# WiFiRadio.net
KiCad netlist of a schematic drawn in EAGLE
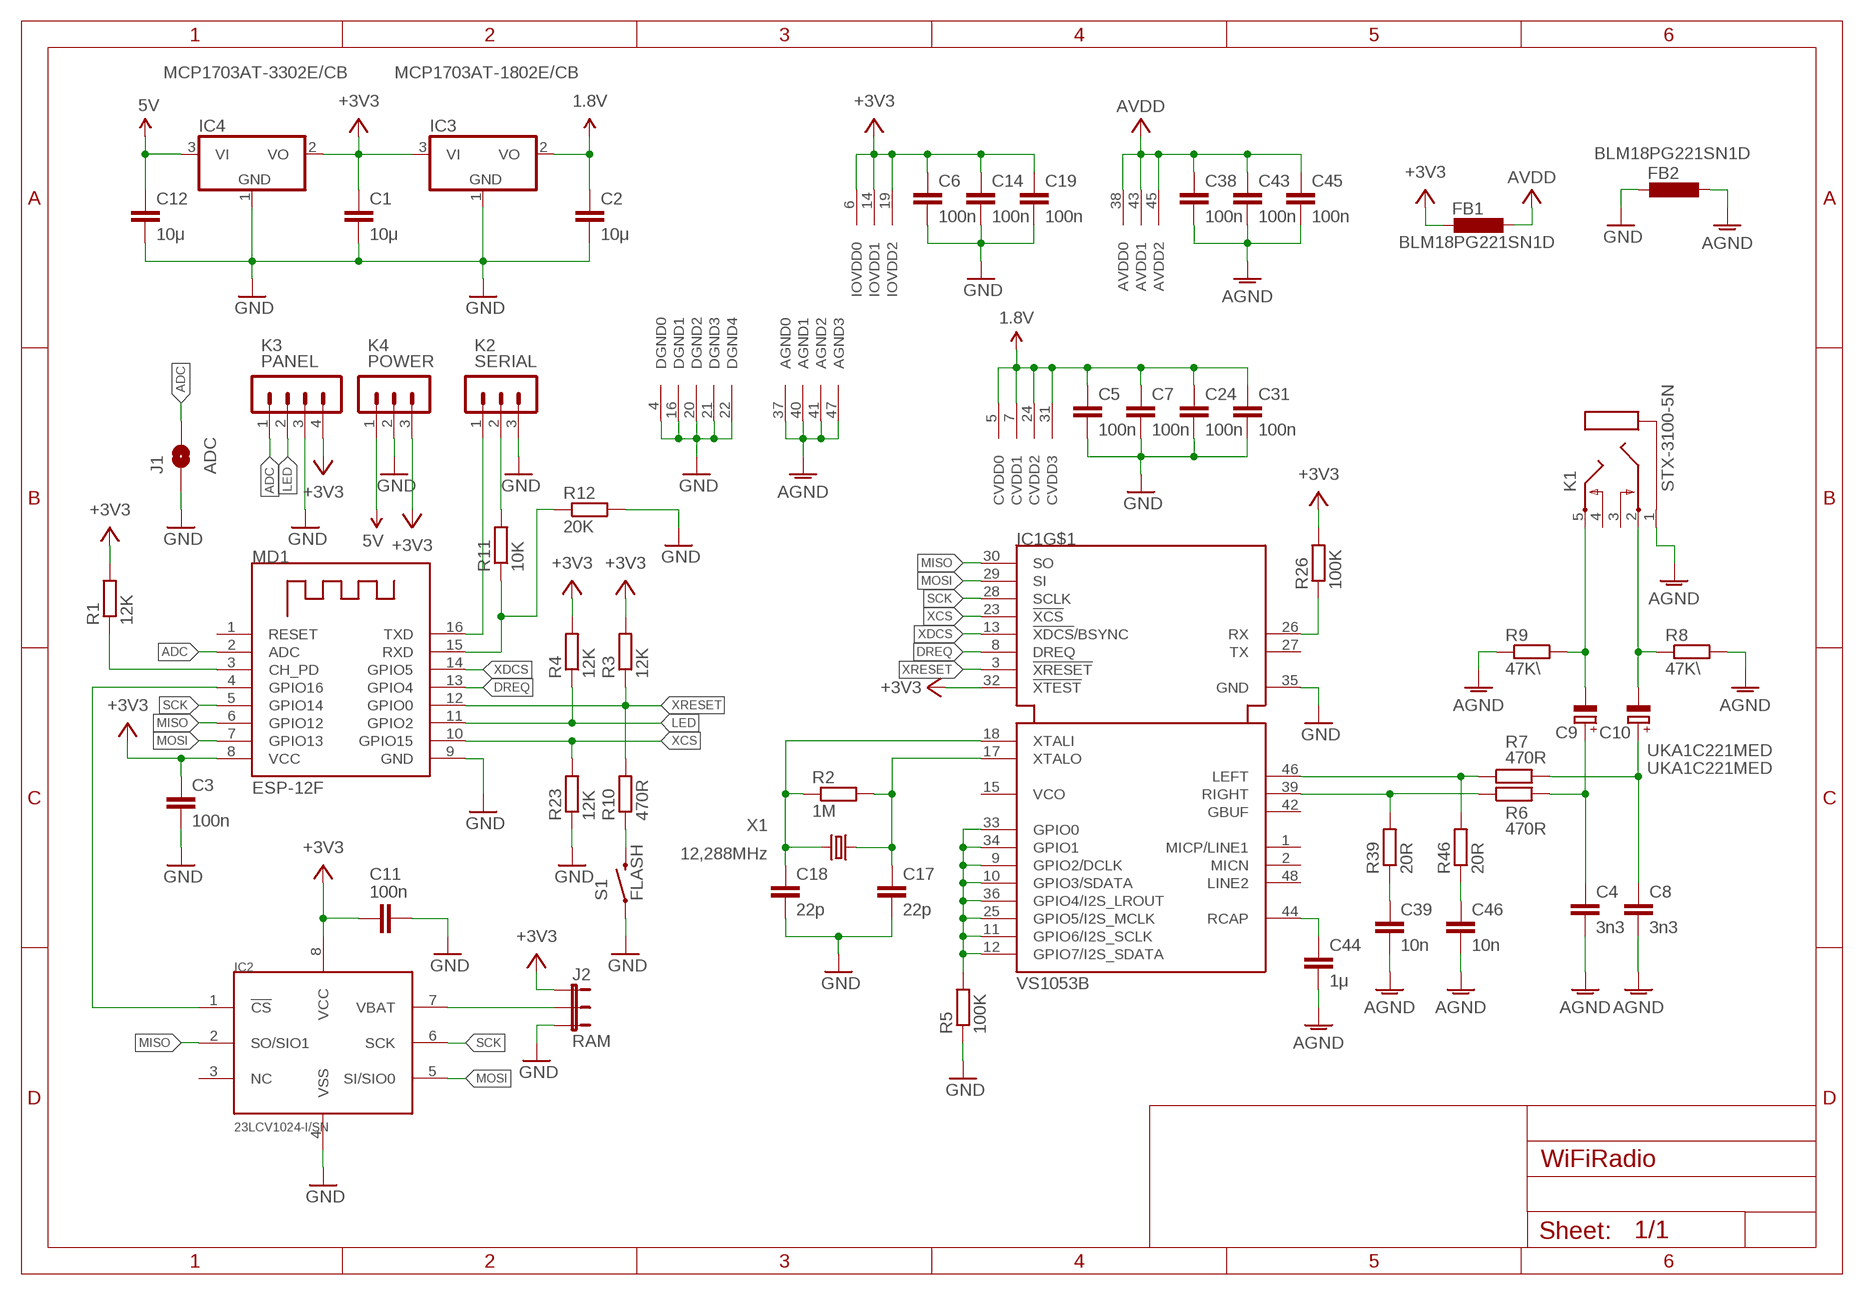
[diagram p0: schematic, sheet 1]

(export (version "E")
  (design (tool "Eeschema 10.0.6"))
  (components
    (comp (ref "C1")
      (value "10μ")
      (footprint "eagle-import:C0805")
      (libsource (lib "eagle-import") (part "C-EUC0805"))
    )
    (comp (ref "C2")
      (value "10μ")
      (footprint "eagle-import:C0805")
      (libsource (lib "eagle-import") (part "C-EUC0805"))
    )
    (comp (ref "C3")
      (value "100n")
      (footprint "eagle-import:C0603")
      (libsource (lib "eagle-import") (part "C-EUC0603"))
    )
    (comp (ref "C4")
      (value "3n3")
      (footprint "eagle-import:C0805")
      (libsource (lib "eagle-import") (part "C-EUC0805"))
    )
    (comp (ref "C5")
      (value "100n")
      (footprint "eagle-import:C0603")
      (libsource (lib "eagle-import") (part "C-EUC0603"))
    )
    (comp (ref "C6")
      (value "100n")
      (footprint "eagle-import:C0603")
      (libsource (lib "eagle-import") (part "C-EUC0603"))
    )
    (comp (ref "C7")
      (value "100n")
      (footprint "eagle-import:C0603")
      (libsource (lib "eagle-import") (part "C-EUC0603"))
    )
    (comp (ref "C8")
      (value "3n3")
      (footprint "eagle-import:C0805")
      (libsource (lib "eagle-import") (part "C-EUC0805"))
    )
    (comp (ref "C9")
      (value "UKA1C221MED")
      (footprint "eagle-import:E2,5-7")
      (libsource (lib "eagle-import") (part "CPOL-EUE2.5-7"))
    )
    (comp (ref "C10")
      (value "UKA1C221MED")
      (footprint "eagle-import:E2,5-7")
      (libsource (lib "eagle-import") (part "CPOL-EUE2.5-7"))
    )
    (comp (ref "C11")
      (value "100n")
      (footprint "eagle-import:C0603")
      (libsource (lib "eagle-import") (part "C-EUC0603"))
    )
    (comp (ref "C12")
      (value "10μ")
      (footprint "eagle-import:C0805")
      (libsource (lib "eagle-import") (part "C-EUC0805"))
    )
    (comp (ref "C14")
      (value "100n")
      (footprint "eagle-import:C0603")
      (libsource (lib "eagle-import") (part "C-EUC0603"))
    )
    (comp (ref "C17")
      (value "22p")
      (footprint "eagle-import:C0805")
      (libsource (lib "eagle-import") (part "C-EUC0805"))
    )
    (comp (ref "C18")
      (value "22p")
      (footprint "eagle-import:C0805")
      (libsource (lib "eagle-import") (part "C-EUC0805"))
    )
    (comp (ref "C19")
      (value "100n")
      (footprint "eagle-import:C0603")
      (libsource (lib "eagle-import") (part "C-EUC0603"))
    )
    (comp (ref "C24")
      (value "100n")
      (footprint "eagle-import:C0603")
      (libsource (lib "eagle-import") (part "C-EUC0603"))
    )
    (comp (ref "C31")
      (value "100n")
      (footprint "eagle-import:C0603")
      (libsource (lib "eagle-import") (part "C-EUC0603"))
    )
    (comp (ref "C38")
      (value "100n")
      (footprint "eagle-import:C0603")
      (libsource (lib "eagle-import") (part "C-EUC0603"))
    )
    (comp (ref "C39")
      (value "10n")
      (footprint "eagle-import:C0805")
      (libsource (lib "eagle-import") (part "C-EUC0805"))
    )
    (comp (ref "C43")
      (value "100n")
      (footprint "eagle-import:C0603")
      (libsource (lib "eagle-import") (part "C-EUC0603"))
    )
    (comp (ref "C44")
      (value "1μ")
      (footprint "eagle-import:C0805")
      (libsource (lib "eagle-import") (part "C-EUC0805"))
    )
    (comp (ref "C45")
      (value "100n")
      (footprint "eagle-import:C0603")
      (libsource (lib "eagle-import") (part "C-EUC0603"))
    )
    (comp (ref "C46")
      (value "10n")
      (footprint "eagle-import:C0805")
      (libsource (lib "eagle-import") (part "C-EUC0805"))
    )
    (comp (ref "FB1")
      (value "BLM18PG221SN1D")
      (footprint "eagle-import:L2012C")
      (libsource (lib "eagle-import") (part "L-EUL2012C"))
    )
    (comp (ref "FB2")
      (value "BLM18PG221SN1D")
      (footprint "eagle-import:L2012C")
      (libsource (lib "eagle-import") (part "L-EUL2012C"))
    )
    (comp (ref "IC1")
      (value "VS1053B")
      (footprint "eagle-import:LQFP48")
      (libsource (lib "eagle-import") (part "VS1053B"))
    )
    (comp (ref "IC2")
      (value "23LCV1024-I/SN")
      (footprint "eagle-import:SO-08")
      (libsource (lib "eagle-import") (part "23LCV1024-I/SN"))
    )
    (comp (ref "IC3")
      (value "MCP1703AT-1802E/CB")
      (footprint "eagle-import:SOT23")
      (libsource (lib "eagle-import") (part "MCP1703CB"))
    )
    (comp (ref "IC4")
      (value "MCP1703AT-3302E/CB")
      (footprint "eagle-import:SOT23")
      (libsource (lib "eagle-import") (part "MCP1703CB"))
    )
    (comp (ref "J1")
      (value "ADC")
      (footprint "eagle-import:SJ_2S")
      (libsource (lib "eagle-import") (part "SOLDERJUMPER-OLDNC"))
    )
    (comp (ref "J2")
      (value "RAM")
      (footprint "eagle-import:SJ_3")
      (libsource (lib "eagle-import") (part "JUMPER-3SMD"))
    )
    (comp (ref "K1")
      (value "STX-3100-5N")
      (footprint "eagle-import:STX3100")
      (libsource (lib "eagle-import") (part "STEREOJACK"))
    )
    (comp (ref "K2")
      (value "SERIAL")
      (footprint "eagle-import:MA03-1")
      (libsource (lib "eagle-import") (part "MA03-1"))
    )
    (comp (ref "K3")
      (value "PANEL")
      (footprint "eagle-import:MA04-1")
      (libsource (lib "eagle-import") (part "MA04-1"))
    )
    (comp (ref "K4")
      (value "POWER")
      (footprint "eagle-import:MA03-1")
      (libsource (lib "eagle-import") (part "MA03-1"))
    )
    (comp (ref "MD1")
      (value "ESP-12F")
      (footprint "eagle-import:ESP-12F")
      (libsource (lib "eagle-import") (part "ESP-12F"))
    )
    (comp (ref "R1")
      (value "12K")
      (footprint "eagle-import:R0805")
      (libsource (lib "eagle-import") (part "R-EU_R0805"))
    )
    (comp (ref "R2")
      (value "1M")
      (footprint "eagle-import:R0805")
      (libsource (lib "eagle-import") (part "R-EU_R0805"))
    )
    (comp (ref "R3")
      (value "12K")
      (footprint "eagle-import:R0805")
      (libsource (lib "eagle-import") (part "R-EU_R0805"))
    )
    (comp (ref "R4")
      (value "12K")
      (footprint "eagle-import:R0805")
      (libsource (lib "eagle-import") (part "R-EU_R0805"))
    )
    (comp (ref "R5")
      (value "100K")
      (footprint "eagle-import:R0805")
      (libsource (lib "eagle-import") (part "R-EU_R0805"))
    )
    (comp (ref "R6")
      (value "470R")
      (footprint "eagle-import:R0805")
      (libsource (lib "eagle-import") (part "R-EU_R0805"))
    )
    (comp (ref "R7")
      (value "470R")
      (footprint "eagle-import:R0805")
      (libsource (lib "eagle-import") (part "R-EU_R0805"))
    )
    (comp (ref "R8")
      (value "47K\\")
      (footprint "eagle-import:R0805")
      (libsource (lib "eagle-import") (part "R-EU_R0805"))
    )
    (comp (ref "R9")
      (value "47K\\")
      (footprint "eagle-import:R0805")
      (libsource (lib "eagle-import") (part "R-EU_R0805"))
    )
    (comp (ref "R10")
      (value "470R")
      (footprint "eagle-import:R0805")
      (libsource (lib "eagle-import") (part "R-EU_R0805"))
    )
    (comp (ref "R11")
      (value "10K")
      (footprint "eagle-import:R0603")
      (libsource (lib "eagle-import") (part "R-EU_R0603"))
    )
    (comp (ref "R12")
      (value "20K")
      (footprint "eagle-import:R0603")
      (libsource (lib "eagle-import") (part "R-EU_R0603"))
    )
    (comp (ref "R23")
      (value "12K")
      (footprint "eagle-import:R0805")
      (libsource (lib "eagle-import") (part "R-EU_R0805"))
    )
    (comp (ref "R26")
      (value "100K")
      (footprint "eagle-import:R0805")
      (libsource (lib "eagle-import") (part "R-EU_R0805"))
    )
    (comp (ref "R39")
      (value "20R")
      (footprint "eagle-import:R0805")
      (libsource (lib "eagle-import") (part "R-EU_R0805"))
    )
    (comp (ref "R46")
      (value "20R")
      (footprint "eagle-import:R0805")
      (libsource (lib "eagle-import") (part "R-EU_R0805"))
    )
    (comp (ref "S1")
      (value "FLASH")
      (footprint "eagle-import:TACTILE-SWITCH-SMD")
      (libsource (lib "eagle-import") (part "SWITCH-MOMENTARY-2SMD"))
    )
    (comp (ref "X1")
      (value "12,288MHz")
      (footprint "eagle-import:HC49_S")
      (libsource (lib "eagle-import") (part "CRYSTALHC49S"))
    )
  )
  (nets
    (net (code "1") (name "+3V3") (class "Default")
      (node (ref "C1") (pin "1") (pinfunction "1_1") (pintype "passive"))
      (node (ref "C11") (pin "1") (pinfunction "1_1") (pintype "passive"))
      (node (ref "C14") (pin "1") (pinfunction "1_1") (pintype "passive"))
      (node (ref "C19") (pin "1") (pinfunction "1_1") (pintype "passive"))
      (node (ref "C3") (pin "1") (pinfunction "1_1") (pintype "passive"))
      (node (ref "C6") (pin "1") (pinfunction "1_1") (pintype "passive"))
      (node (ref "FB1") (pin "2") (pinfunction "2_2") (pintype "passive"))
      (node (ref "IC1") (pin "14") (pinfunction "IOVDD1_14") (pintype "power_in"))
      (node (ref "IC1") (pin "19") (pinfunction "IOVDD2_19") (pintype "power_in"))
      (node (ref "IC1") (pin "32") (pinfunction "~{XTEST}_32") (pintype "input"))
      (node (ref "IC1") (pin "6") (pinfunction "IOVDD0_6") (pintype "power_in"))
      (node (ref "IC2") (pin "8") (pinfunction "VCC_8") (pintype "power_in"))
      (node (ref "IC3") (pin "3") (pinfunction "VI_3") (pintype "input"))
      (node (ref "IC4") (pin "2") (pinfunction "VO_2") (pintype "passive"))
      (node (ref "J2") (pin "1") (pinfunction "1_1") (pintype "passive"))
      (node (ref "K3") (pin "4") (pinfunction "4_4") (pintype "passive"))
      (node (ref "K4") (pin "3") (pinfunction "3_3") (pintype "passive"))
      (node (ref "MD1") (pin "8") (pinfunction "VCC_8") (pintype "power_in"))
      (node (ref "R1") (pin "2") (pinfunction "2_2") (pintype "passive"))
      (node (ref "R26") (pin "2") (pinfunction "2_2") (pintype "passive"))
      (node (ref "R3") (pin "2") (pinfunction "2_2") (pintype "passive"))
      (node (ref "R4") (pin "2") (pinfunction "2_2") (pintype "passive"))
    )
    (net (code "2") (name "1.8V") (class "Default")
      (node (ref "C2") (pin "1") (pinfunction "1_1") (pintype "passive"))
      (node (ref "C24") (pin "1") (pinfunction "1_1") (pintype "passive"))
      (node (ref "C31") (pin "1") (pinfunction "1_1") (pintype "passive"))
      (node (ref "C5") (pin "1") (pinfunction "1_1") (pintype "passive"))
      (node (ref "C7") (pin "1") (pinfunction "1_1") (pintype "passive"))
      (node (ref "IC1") (pin "24") (pinfunction "CVDD2_24") (pintype "power_in"))
      (node (ref "IC1") (pin "31") (pinfunction "CVDD3_31") (pintype "power_in"))
      (node (ref "IC1") (pin "5") (pinfunction "CVDD0_5") (pintype "power_in"))
      (node (ref "IC1") (pin "7") (pinfunction "CVDD1_7") (pintype "power_in"))
      (node (ref "IC3") (pin "2") (pinfunction "VO_2") (pintype "passive"))
    )
    (net (code "3") (name "5V") (class "Default")
      (node (ref "C12") (pin "1") (pinfunction "1_1") (pintype "passive"))
      (node (ref "IC4") (pin "3") (pinfunction "VI_3") (pintype "input"))
      (node (ref "K4") (pin "1") (pinfunction "1_1") (pintype "passive"))
    )
    (net (code "4") (name "ADC") (class "Default")
      (node (ref "J1") (pin "2") (pinfunction "2_2") (pintype "passive"))
      (node (ref "K3") (pin "1") (pinfunction "1_1") (pintype "passive"))
      (node (ref "MD1") (pin "2") (pinfunction "ADC_2") (pintype "passive"))
    )
    (net (code "5") (name "AGND") (class "Default")
      (node (ref "C38") (pin "2") (pinfunction "2_2") (pintype "passive"))
      (node (ref "C39") (pin "2") (pinfunction "2_2") (pintype "passive"))
      (node (ref "C4") (pin "2") (pinfunction "2_2") (pintype "passive"))
      (node (ref "C43") (pin "2") (pinfunction "2_2") (pintype "passive"))
      (node (ref "C44") (pin "2") (pinfunction "2_2") (pintype "passive"))
      (node (ref "C45") (pin "2") (pinfunction "2_2") (pintype "passive"))
      (node (ref "C46") (pin "2") (pinfunction "2_2") (pintype "passive"))
      (node (ref "C8") (pin "2") (pinfunction "2_2") (pintype "passive"))
      (node (ref "FB2") (pin "1") (pinfunction "1_1") (pintype "passive"))
      (node (ref "IC1") (pin "37") (pinfunction "AGND0_37") (pintype "power_in"))
      (node (ref "IC1") (pin "40") (pinfunction "AGND1_40") (pintype "power_in"))
      (node (ref "IC1") (pin "41") (pinfunction "AGND2_41") (pintype "power_in"))
      (node (ref "IC1") (pin "47") (pinfunction "AGND3_47") (pintype "power_in"))
      (node (ref "K1") (pin "1") (pinfunction "1_1") (pintype "passive"))
      (node (ref "R8") (pin "2") (pinfunction "2_2") (pintype "passive"))
      (node (ref "R9") (pin "1") (pinfunction "1_1") (pintype "passive"))
    )
    (net (code "6") (name "AVDD") (class "Default")
      (node (ref "C38") (pin "1") (pinfunction "1_1") (pintype "passive"))
      (node (ref "C43") (pin "1") (pinfunction "1_1") (pintype "passive"))
      (node (ref "C45") (pin "1") (pinfunction "1_1") (pintype "passive"))
      (node (ref "FB1") (pin "1") (pinfunction "1_1") (pintype "passive"))
      (node (ref "IC1") (pin "38") (pinfunction "AVDD0_38") (pintype "power_in"))
      (node (ref "IC1") (pin "43") (pinfunction "AVDD1_43") (pintype "power_in"))
      (node (ref "IC1") (pin "45") (pinfunction "AVDD2_45") (pintype "power_in"))
    )
    (net (code "7") (name "DREQ") (class "Default")
      (node (ref "IC1") (pin "8") (pinfunction "DREQ_8") (pintype "output"))
      (node (ref "MD1") (pin "13") (pinfunction "GPIO4_13") (pintype "bidirectional"))
    )
    (net (code "8") (name "GND") (class "Default")
      (node (ref "C1") (pin "2") (pinfunction "2_2") (pintype "passive"))
      (node (ref "C11") (pin "2") (pinfunction "2_2") (pintype "passive"))
      (node (ref "C12") (pin "2") (pinfunction "2_2") (pintype "passive"))
      (node (ref "C14") (pin "2") (pinfunction "2_2") (pintype "passive"))
      (node (ref "C17") (pin "2") (pinfunction "2_2") (pintype "passive"))
      (node (ref "C18") (pin "2") (pinfunction "2_2") (pintype "passive"))
      (node (ref "C19") (pin "2") (pinfunction "2_2") (pintype "passive"))
      (node (ref "C2") (pin "2") (pinfunction "2_2") (pintype "passive"))
      (node (ref "C24") (pin "2") (pinfunction "2_2") (pintype "passive"))
      (node (ref "C3") (pin "2") (pinfunction "2_2") (pintype "passive"))
      (node (ref "C31") (pin "2") (pinfunction "2_2") (pintype "passive"))
      (node (ref "C5") (pin "2") (pinfunction "2_2") (pintype "passive"))
      (node (ref "C6") (pin "2") (pinfunction "2_2") (pintype "passive"))
      (node (ref "C7") (pin "2") (pinfunction "2_2") (pintype "passive"))
      (node (ref "FB2") (pin "2") (pinfunction "2_2") (pintype "passive"))
      (node (ref "IC1") (pin "16") (pinfunction "DGND1_16") (pintype "power_in"))
      (node (ref "IC1") (pin "20") (pinfunction "DGND2_20") (pintype "power_in"))
      (node (ref "IC1") (pin "21") (pinfunction "DGND3_21") (pintype "power_in"))
      (node (ref "IC1") (pin "22") (pinfunction "DGND4_22") (pintype "power_in"))
      (node (ref "IC1") (pin "35") (pinfunction "GND_35") (pintype "power_in"))
      (node (ref "IC1") (pin "4") (pinfunction "DGND0_4") (pintype "power_in"))
      (node (ref "IC2") (pin "4") (pinfunction "VSS_4") (pintype "power_in"))
      (node (ref "IC3") (pin "1") (pinfunction "GND_1") (pintype "passive"))
      (node (ref "IC4") (pin "1") (pinfunction "GND_1") (pintype "passive"))
      (node (ref "J1") (pin "1") (pinfunction "1_1") (pintype "passive"))
      (node (ref "J2") (pin "3") (pinfunction "3_3") (pintype "passive"))
      (node (ref "K2") (pin "3") (pinfunction "3_3") (pintype "passive"))
      (node (ref "K3") (pin "3") (pinfunction "3_3") (pintype "passive"))
      (node (ref "K4") (pin "2") (pinfunction "2_2") (pintype "passive"))
      (node (ref "MD1") (pin "9") (pinfunction "GND_9") (pintype "power_in"))
      (node (ref "R12") (pin "2") (pinfunction "2_2") (pintype "passive"))
      (node (ref "R23") (pin "1") (pinfunction "1_1") (pintype "passive"))
      (node (ref "R5") (pin "1") (pinfunction "1_1") (pintype "passive"))
      (node (ref "S1") (pin "1") (pinfunction "1_1") (pintype "passive"))
    )
    (net (code "9") (name "LED") (class "Default")
      (node (ref "K3") (pin "2") (pinfunction "2_2") (pintype "passive"))
      (node (ref "MD1") (pin "11") (pinfunction "GPIO2_11") (pintype "bidirectional"))
      (node (ref "R4") (pin "1") (pinfunction "1_1") (pintype "passive"))
    )
    (net (code "10") (name "MISO") (class "Default")
      (node (ref "IC1") (pin "30") (pinfunction "SO_30") (pintype "output"))
      (node (ref "IC2") (pin "2") (pinfunction "SO/SIO1_2") (pintype "bidirectional"))
      (node (ref "MD1") (pin "6") (pinfunction "GPIO12_6") (pintype "bidirectional"))
    )
    (net (code "11") (name "MOSI") (class "Default")
      (node (ref "IC1") (pin "29") (pinfunction "SI_29") (pintype "input"))
      (node (ref "IC2") (pin "5") (pinfunction "SI/SIO0_5") (pintype "bidirectional"))
      (node (ref "MD1") (pin "7") (pinfunction "GPIO13_7") (pintype "bidirectional"))
    )
    (net (code "12") (name "Net-(C4-Pad1)") (class "Default")
      (node (ref "C4") (pin "1") (pinfunction "1_1") (pintype "passive"))
      (node (ref "C9") (pin "+") (pinfunction "+_+") (pintype "passive"))
      (node (ref "R6") (pin "2") (pinfunction "2_2") (pintype "passive"))
    )
    (net (code "13") (name "Net-(C9-Pad-)") (class "Default")
      (node (ref "C9") (pin "-") (pinfunction "-_-") (pintype "passive"))
      (node (ref "K1") (pin "5") (pinfunction "5_5") (pintype "passive"))
      (node (ref "R9") (pin "2") (pinfunction "2_2") (pintype "passive"))
    )
    (net (code "14") (name "Net-(C10-Pad+)") (class "Default")
      (node (ref "C10") (pin "+") (pinfunction "+_+") (pintype "passive"))
      (node (ref "C8") (pin "1") (pinfunction "1_1") (pintype "passive"))
      (node (ref "R7") (pin "2") (pinfunction "2_2") (pintype "passive"))
    )
    (net (code "15") (name "Net-(C10-Pad-)") (class "Default")
      (node (ref "C10") (pin "-") (pinfunction "-_-") (pintype "passive"))
      (node (ref "K1") (pin "2") (pinfunction "2_2") (pintype "passive"))
      (node (ref "R8") (pin "1") (pinfunction "1_1") (pintype "passive"))
    )
    (net (code "16") (name "Net-(C39-Pad1)") (class "Default")
      (node (ref "C39") (pin "1") (pinfunction "1_1") (pintype "passive"))
      (node (ref "R39") (pin "1") (pinfunction "1_1") (pintype "passive"))
    )
    (net (code "17") (name "Net-(C46-Pad1)") (class "Default")
      (node (ref "C46") (pin "1") (pinfunction "1_1") (pintype "passive"))
      (node (ref "R46") (pin "1") (pinfunction "1_1") (pintype "passive"))
    )
    (net (code "18") (name "Net-(IC1A-GPIO0)") (class "Default")
      (node (ref "IC1") (pin "10") (pinfunction "GPIO3/SDATA_10") (pintype "bidirectional"))
      (node (ref "IC1") (pin "11") (pinfunction "GPIO6/I2S_SCLK_11") (pintype "bidirectional"))
      (node (ref "IC1") (pin "12") (pinfunction "GPIO7/I2S_SDATA_12") (pintype "bidirectional"))
      (node (ref "IC1") (pin "25") (pinfunction "GPIO5/I2S_MCLK_25") (pintype "bidirectional"))
      (node (ref "IC1") (pin "33") (pinfunction "GPIO0_33") (pintype "bidirectional"))
      (node (ref "IC1") (pin "34") (pinfunction "GPIO1_34") (pintype "bidirectional"))
      (node (ref "IC1") (pin "36") (pinfunction "GPIO4/I2S_LROUT_36") (pintype "bidirectional"))
      (node (ref "IC1") (pin "9") (pinfunction "GPIO2/DCLK_9") (pintype "bidirectional"))
      (node (ref "R5") (pin "2") (pinfunction "2_2") (pintype "passive"))
    )
    (net (code "19") (name "Net-(IC1A-LEFT)") (class "Default")
      (node (ref "IC1") (pin "46") (pinfunction "LEFT_46") (pintype "output"))
      (node (ref "R46") (pin "2") (pinfunction "2_2") (pintype "passive"))
      (node (ref "R7") (pin "1") (pinfunction "1_1") (pintype "passive"))
    )
    (net (code "20") (name "Net-(IC1A-RCAP)") (class "Default")
      (node (ref "C44") (pin "1") (pinfunction "1_1") (pintype "passive"))
      (node (ref "IC1") (pin "44") (pinfunction "RCAP_44") (pintype "bidirectional"))
    )
    (net (code "21") (name "Net-(IC1A-RIGHT)") (class "Default")
      (node (ref "IC1") (pin "39") (pinfunction "RIGHT_39") (pintype "output"))
      (node (ref "R39") (pin "2") (pinfunction "2_2") (pintype "passive"))
      (node (ref "R6") (pin "1") (pinfunction "1_1") (pintype "passive"))
    )
    (net (code "22") (name "Net-(IC1A-RX)") (class "Default")
      (node (ref "IC1") (pin "26") (pinfunction "RX_26") (pintype "input"))
      (node (ref "R26") (pin "1") (pinfunction "1_1") (pintype "passive"))
    )
    (net (code "23") (name "Net-(IC1A-XTALI)") (class "Default")
      (node (ref "C18") (pin "1") (pinfunction "1_1") (pintype "passive"))
      (node (ref "IC1") (pin "18") (pinfunction "XTALI_18") (pintype "input"))
      (node (ref "R2") (pin "1") (pinfunction "1_1") (pintype "passive"))
      (node (ref "X1") (pin "2") (pinfunction "2_2") (pintype "passive"))
    )
    (net (code "24") (name "Net-(IC1A-XTALO)") (class "Default")
      (node (ref "C17") (pin "1") (pinfunction "1_1") (pintype "passive"))
      (node (ref "IC1") (pin "17") (pinfunction "XTALO_17") (pintype "output"))
      (node (ref "R2") (pin "2") (pinfunction "2_2") (pintype "passive"))
      (node (ref "X1") (pin "1") (pinfunction "1_1") (pintype "passive"))
    )
    (net (code "25") (name "Net-(IC2-VBAT)") (class "Default")
      (node (ref "IC2") (pin "7") (pinfunction "VBAT_7") (pintype "power_in"))
      (node (ref "J2") (pin "2") (pinfunction "2_2") (pintype "passive"))
    )
    (net (code "26") (name "Net-(IC2-~{CS})") (class "Default")
      (node (ref "IC2") (pin "1") (pinfunction "~{CS}_1") (pintype "input"))
      (node (ref "MD1") (pin "4") (pinfunction "GPIO16_4") (pintype "bidirectional"))
    )
    (net (code "27") (name "Net-(K2-Pad2)") (class "Default")
      (node (ref "K2") (pin "2") (pinfunction "2_2") (pintype "passive"))
      (node (ref "R11") (pin "2") (pinfunction "2_2") (pintype "passive"))
    )
    (net (code "28") (name "Net-(MD1-CH_PD)") (class "Default")
      (node (ref "MD1") (pin "3") (pinfunction "CH_PD_3") (pintype "input"))
      (node (ref "R1") (pin "1") (pinfunction "1_1") (pintype "passive"))
    )
    (net (code "29") (name "Net-(MD1-RXD)") (class "Default")
      (node (ref "MD1") (pin "15") (pinfunction "RXD_15") (pintype "input"))
      (node (ref "R11") (pin "1") (pinfunction "1_1") (pintype "passive"))
      (node (ref "R12") (pin "1") (pinfunction "1_1") (pintype "passive"))
    )
    (net (code "30") (name "Net-(MD1-TXD)") (class "Default")
      (node (ref "K2") (pin "1") (pinfunction "1_1") (pintype "passive"))
      (node (ref "MD1") (pin "16") (pinfunction "TXD_16") (pintype "output"))
    )
    (net (code "31") (name "Net-(S1-2)") (class "Default")
      (node (ref "R10") (pin "1") (pinfunction "1_1") (pintype "passive"))
      (node (ref "S1") (pin "3") (pinfunction "2_3") (pintype "passive"))
    )
    (net (code "32") (name "SCK") (class "Default")
      (node (ref "IC1") (pin "28") (pinfunction "SCLK_28") (pintype "input"))
      (node (ref "IC2") (pin "6") (pinfunction "SCK_6") (pintype "input"))
      (node (ref "MD1") (pin "5") (pinfunction "GPIO14_5") (pintype "bidirectional"))
    )
    (net (code "33") (name "XCS") (class "Default")
      (node (ref "IC1") (pin "23") (pinfunction "~{XCS}_23") (pintype "input"))
      (node (ref "MD1") (pin "10") (pinfunction "GPIO15_10") (pintype "bidirectional"))
      (node (ref "R23") (pin "2") (pinfunction "2_2") (pintype "passive"))
    )
    (net (code "34") (name "XDCS") (class "Default")
      (node (ref "IC1") (pin "13") (pinfunction "~{XDCS}/BSYNC_13") (pintype "input"))
      (node (ref "MD1") (pin "14") (pinfunction "GPIO5_14") (pintype "bidirectional"))
    )
    (net (code "35") (name "XRESET") (class "Default")
      (node (ref "IC1") (pin "3") (pinfunction "~{XRESET}_3") (pintype "input"))
      (node (ref "MD1") (pin "12") (pinfunction "GPIO0_12") (pintype "bidirectional"))
      (node (ref "R10") (pin "2") (pinfunction "2_2") (pintype "passive"))
      (node (ref "R3") (pin "1") (pinfunction "1_1") (pintype "passive"))
    )
    (net (code "36") (name "unconnected-(IC1A-GBUF-Pad42)") (class "Default")
      (node (ref "IC1") (pin "42") (pinfunction "GBUF_42") (pintype "output"))
    )
    (net (code "37") (name "unconnected-(IC1A-LINE2-Pad48)") (class "Default")
      (node (ref "IC1") (pin "48") (pinfunction "LINE2_48") (pintype "input"))
    )
    (net (code "38") (name "unconnected-(IC1A-MICN-Pad2)") (class "Default")
      (node (ref "IC1") (pin "2") (pinfunction "MICN_2") (pintype "input"))
    )
    (net (code "39") (name "unconnected-(IC1A-MICP{slash}LINE1-Pad1)") (class "Default")
      (node (ref "IC1") (pin "1") (pinfunction "MICP/LINE1_1") (pintype "input"))
    )
    (net (code "40") (name "unconnected-(IC1A-TX-Pad27)") (class "Default")
      (node (ref "IC1") (pin "27") (pinfunction "TX_27") (pintype "output"))
    )
    (net (code "41") (name "unconnected-(IC1A-VCO-Pad15)") (class "Default")
      (node (ref "IC1") (pin "15") (pinfunction "VCO_15") (pintype "output"))
    )
    (net (code "42") (name "unconnected-(IC2-NC-Pad3)") (class "Default")
      (node (ref "IC2") (pin "3") (pinfunction "NC_3") (pintype "no_connect"))
    )
    (net (code "43") (name "unconnected-(K1-Pad3)") (class "Default")
      (node (ref "K1") (pin "3") (pinfunction "3_3") (pintype "passive"))
    )
    (net (code "44") (name "unconnected-(K1-Pad4)") (class "Default")
      (node (ref "K1") (pin "4") (pinfunction "4_4") (pintype "passive"))
    )
    (net (code "45") (name "unconnected-(MD1-RESET-Pad1)") (class "Default")
      (node (ref "MD1") (pin "1") (pinfunction "RESET_1") (pintype "input"))
    )
  )
)
